# CONN.net
KiCad netlist of a schematic drawn in Altium Designer
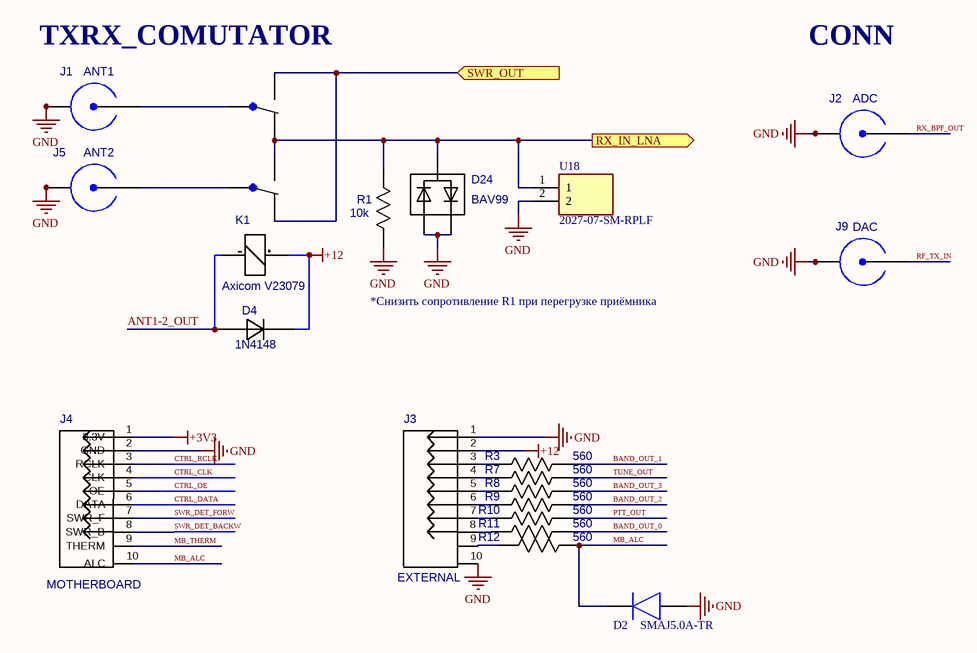
[diagram p0: CONN.SchDoc]

(export (version "E")
  (design (tool "Eeschema 10.0.6"))
  (components
    (comp (ref "D2")
      (value "SMAJ5.0A-TR")
      (footprint "SamacSys:SMBJ36CATR")
      (description "Diode")
      (fields
        (field (name "MANUFACTURER_PART_NUMBER") "SMLVT3V3")
        (field (name "MOUSER PART NUMBER") "511-SMLVT3V3")
      )
      (libsource (lib "*") (part "SMLVT3V3"))
    )
    (comp (ref "D4") (value "1N4148") (footprint "1N4148") (libsource (lib "*") (part "1N4148")))
    (comp (ref "D24") (value "BAV99") (footprint "SOT23") (libsource (lib "*") (part "BAV99")))
    (comp (ref "J1")
      (value "ANT1")
      (footprint "31-5431")
      (description "SMA")
      (libsource (lib "RF-UNIT_1") (part "31-5431"))
    )
    (comp (ref "J2")
      (value "ADC")
      (footprint "31-5431")
      (description "SMA")
      (libsource (lib "RF-UNIT_1") (part "31-5431"))
    )
    (comp (ref "J3")
      (value "EXTERNAL")
      (footprint "90131-0126")
      (description "2*5 PIN")
      (libsource (lib "") (part "90131-0126_1"))
    )
    (comp (ref "J4")
      (value "MOTHERBOARD")
      (footprint "90131-0126")
      (description "2*5 PIN")
      (libsource (lib "RF-UNIT") (part "90131-0126"))
    )
    (comp (ref "J5")
      (value "ANT2")
      (footprint "31-5431")
      (description "SMA")
      (libsource (lib "RF-UNIT_1") (part "31-5431"))
    )
    (comp (ref "J9")
      (value "DAC")
      (footprint "31-5431")
      (description "SMA")
      (libsource (lib "RF-UNIT_1") (part "31-5431"))
    )
    (comp (ref "K1")
      (value "Axicom V23079")
      (footprint "V23079")
      (libsource (lib "RF-UNIT") (part "Axicom V23079"))
    )
    (comp (ref "R1")
      (value "10k")
      (footprint "RES_1206")
      (description "RES_1206")
      (libsource (lib "*") (part "RES_1206"))
    )
    (comp (ref "R3")
      (value "560")
      (footprint "RES_0805")
      (description "RES_0805")
      (libsource (lib "*") (part "RES_0805"))
    )
    (comp (ref "R7")
      (value "560")
      (footprint "RES_0805")
      (description "RES_0805")
      (libsource (lib "*") (part "RES_0805"))
    )
    (comp (ref "R8")
      (value "560")
      (footprint "RES_0805")
      (description "RES_0805")
      (libsource (lib "*") (part "RES_0805"))
    )
    (comp (ref "R9")
      (value "560")
      (footprint "RES_0805")
      (description "RES_0805")
      (libsource (lib "*") (part "RES_0805"))
    )
    (comp (ref "R10")
      (value "560")
      (footprint "RES_0805")
      (description "RES_0805")
      (libsource (lib "*") (part "RES_0805"))
    )
    (comp (ref "R11")
      (value "560")
      (footprint "RES_0805")
      (description "RES_0805")
      (libsource (lib "*") (part "RES_0805"))
    )
    (comp (ref "R12")
      (value "560")
      (footprint "RES_0805")
      (description "RES_0805")
      (libsource (lib "*") (part "RES_0805"))
    )
    (comp (ref "U18")
      (value "2027-07-SM-RPLF")
      (footprint "SamacSys:200307SMRPLF")
      (description "Undefined or Miscellaneous")
      (fields
        (field (name "MANUFACTURER_PART_NUMBER") "2003-07-SM-RPLF")
        (field (name "MOUSER PART NUMBER") "652-2003-07-SM-RPLF")
      )
      (libsource (lib "*") (part "2003-07-SM-RPLF"))
    )
  )
  (nets
    (net (code "1") (name "+3V3") (class "Default")
      (node (ref "J4") (pin "1") (pinfunction "3.3V_1") (pintype "passive"))
    )
    (net (code "2") (name "+12") (class "Default")
      (node (ref "D4") (pin "1") (pinfunction "K_1") (pintype "passive"))
      (node (ref "J3") (pin "2") (pinfunction "12V_2") (pintype "passive"))
      (node (ref "K1") (pin "1") (pinfunction "+_1") (pintype "passive"))
    )
    (net (code "4") (name "/ANT1-2_OUT") (class "Default")
      (node (ref "D4") (pin "2") (pinfunction "A_2") (pintype "passive"))
      (node (ref "K1") (pin "8") (pinfunction "-_8") (pintype "passive"))
    )
    (net (code "5") (name "/BAND_OUT_0") (class "Default")
      (node (ref "R11") (pin "2") (pinfunction "2_2") (pintype "passive"))
    )
    (net (code "6") (name "/BAND_OUT_1") (class "Default")
      (node (ref "R3") (pin "2") (pinfunction "2_2") (pintype "passive"))
    )
    (net (code "7") (name "/BAND_OUT_2") (class "Default")
      (node (ref "R9") (pin "2") (pinfunction "2_2") (pintype "passive"))
    )
    (net (code "8") (name "/BAND_OUT_3") (class "Default")
      (node (ref "R8") (pin "2") (pinfunction "2_2") (pintype "passive"))
    )
    (net (code "9") (name "/CTRL_CLK") (class "Default")
      (node (ref "J4") (pin "4") (pinfunction "CLK_4") (pintype "passive"))
    )
    (net (code "10") (name "/CTRL_DATA") (class "Default")
      (node (ref "J4") (pin "6") (pinfunction "DATA_6") (pintype "passive"))
    )
    (net (code "11") (name "/CTRL_OE") (class "Default")
      (node (ref "J4") (pin "5") (pinfunction "OE_5") (pintype "passive"))
    )
    (net (code "12") (name "/CTRL_RCLK") (class "Default")
      (node (ref "J4") (pin "3") (pinfunction "RCLK_3") (pintype "passive"))
    )
    (net (code "13") (name "/MB_ALC") (class "Default")
      (node (ref "D2") (pin "1") (pinfunction "K_1") (pintype "passive"))
      (node (ref "J4") (pin "10") (pinfunction "ALC_10") (pintype "passive"))
      (node (ref "R12") (pin "2") (pinfunction "2_2") (pintype "passive"))
    )
    (net (code "14") (name "/MB_THERM") (class "Default")
      (node (ref "J4") (pin "9") (pinfunction "THERM_9") (pintype "passive"))
    )
    (net (code "15") (name "/PTT_OUT") (class "Default")
      (node (ref "R10") (pin "2") (pinfunction "2_2") (pintype "passive"))
    )
    (net (code "16") (name "/RF_TX_IN") (class "Default")
      (node (ref "J9") (pin "5") (pinfunction "CON_5") (pintype "passive"))
    )
    (net (code "17") (name "/RX_BPF_OUT") (class "Default")
      (node (ref "J2") (pin "5") (pinfunction "CON_5") (pintype "passive"))
    )
    (net (code "18") (name "/RX_IN_LNA") (class "Default")
      (node (ref "D24") (pin "3") (pinfunction "C(D1),A(D2)_3") (pintype "passive"))
      (node (ref "K1") (pin "4") (pinfunction "S_4") (pintype "passive"))
      (node (ref "K1") (pin "7") (pinfunction "O_7") (pintype "passive"))
      (node (ref "R1") (pin "2") (pinfunction "2_2") (pintype "passive"))
      (node (ref "U18") (pin "1") (pinfunction "1_1") (pintype "passive"))
    )
    (net (code "19") (name "/SWR_DET_BACKW") (class "Default")
      (node (ref "J4") (pin "8") (pinfunction "SWR_B_8") (pintype "passive"))
    )
    (net (code "20") (name "/SWR_DET_FORW") (class "Default")
      (node (ref "J4") (pin "7") (pinfunction "SWR_F_7") (pintype "passive"))
    )
    (net (code "21") (name "/SWR_OUT") (class "Default")
      (node (ref "K1") (pin "2") (pinfunction "O_2") (pintype "passive"))
      (node (ref "K1") (pin "5") (pinfunction "S_5") (pintype "passive"))
    )
    (net (code "22") (name "/TUNE_OUT") (class "Default")
      (node (ref "R7") (pin "2") (pinfunction "2_2") (pintype "passive"))
    )
    (net (code "23") (name "GND") (class "Default")
      (node (ref "D2") (pin "2") (pinfunction "A_2") (pintype "passive"))
      (node (ref "D24") (pin "1") (pinfunction "A(D1)_1") (pintype "passive"))
      (node (ref "D24") (pin "2") (pinfunction "C(D2)_2") (pintype "passive"))
      (node (ref "J1") (pin "1") (pinfunction "GND_1") (pintype "passive"))
      (node (ref "J1") (pin "2") (pinfunction "GND_2") (pintype "passive"))
      (node (ref "J1") (pin "3") (pinfunction "GND_3") (pintype "passive"))
      (node (ref "J1") (pin "4") (pinfunction "GND_4") (pintype "passive"))
      (node (ref "J2") (pin "1") (pinfunction "GND_1") (pintype "passive"))
      (node (ref "J2") (pin "2") (pinfunction "GND_2") (pintype "passive"))
      (node (ref "J2") (pin "3") (pinfunction "GND_3") (pintype "passive"))
      (node (ref "J2") (pin "4") (pinfunction "GND_4") (pintype "passive"))
      (node (ref "J3") (pin "1") (pinfunction "GND_1") (pintype "passive"))
      (node (ref "J3") (pin "10") (pinfunction "GND_10") (pintype "passive"))
      (node (ref "J4") (pin "2") (pinfunction "GND_2") (pintype "passive"))
      (node (ref "J5") (pin "1") (pinfunction "GND_1") (pintype "passive"))
      (node (ref "J5") (pin "2") (pinfunction "GND_2") (pintype "passive"))
      (node (ref "J5") (pin "3") (pinfunction "GND_3") (pintype "passive"))
      (node (ref "J5") (pin "4") (pinfunction "GND_4") (pintype "passive"))
      (node (ref "J9") (pin "1") (pinfunction "GND_1") (pintype "passive"))
      (node (ref "J9") (pin "2") (pinfunction "GND_2") (pintype "passive"))
      (node (ref "J9") (pin "3") (pinfunction "GND_3") (pintype "passive"))
      (node (ref "J9") (pin "4") (pinfunction "GND_4") (pintype "passive"))
      (node (ref "R1") (pin "1") (pinfunction "1_1") (pintype "passive"))
      (node (ref "U18") (pin "2") (pinfunction "2_2") (pintype "passive"))
    )
    (net (code "24") (name "Net-(J1-CON)") (class "Default")
      (node (ref "J1") (pin "5") (pinfunction "CON_5") (pintype "passive"))
      (node (ref "K1") (pin "6") (pinfunction "P_6") (pintype "passive"))
    )
    (net (code "25") (name "Net-(J3-ALC_IN)") (class "Default")
      (node (ref "J3") (pin "9") (pinfunction "ALC_IN_9") (pintype "passive"))
      (node (ref "R12") (pin "1") (pinfunction "1_1") (pintype "passive"))
    )
    (net (code "26") (name "Net-(J3-BAND0)") (class "Default")
      (node (ref "J3") (pin "8") (pinfunction "BAND0_8") (pintype "passive"))
      (node (ref "R11") (pin "1") (pinfunction "1_1") (pintype "passive"))
    )
    (net (code "27") (name "Net-(J3-BAND1)") (class "Default")
      (node (ref "J3") (pin "3") (pinfunction "BAND1_3") (pintype "passive"))
      (node (ref "R3") (pin "1") (pinfunction "1_1") (pintype "passive"))
    )
    (net (code "28") (name "Net-(J3-BAND2)") (class "Default")
      (node (ref "J3") (pin "6") (pinfunction "BAND2_6") (pintype "passive"))
      (node (ref "R9") (pin "1") (pinfunction "1_1") (pintype "passive"))
    )
    (net (code "29") (name "Net-(J3-BAND3)") (class "Default")
      (node (ref "J3") (pin "5") (pinfunction "BAND3_5") (pintype "passive"))
      (node (ref "R8") (pin "1") (pinfunction "1_1") (pintype "passive"))
    )
    (net (code "30") (name "Net-(J3-PTT_OUT)") (class "Default")
      (node (ref "J3") (pin "7") (pinfunction "PTT_OUT_7") (pintype "passive"))
      (node (ref "R10") (pin "1") (pinfunction "1_1") (pintype "passive"))
    )
    (net (code "31") (name "Net-(J3-TUNE_OUT)") (class "Default")
      (node (ref "J3") (pin "4") (pinfunction "TUNE_OUT_4") (pintype "passive"))
      (node (ref "R7") (pin "1") (pinfunction "1_1") (pintype "passive"))
    )
    (net (code "32") (name "Net-(J5-CON)") (class "Default")
      (node (ref "J5") (pin "5") (pinfunction "CON_5") (pintype "passive"))
      (node (ref "K1") (pin "3") (pinfunction "P_3") (pintype "passive"))
    )
  )
)
